# HLib-Comm-RS485.net
KiCad netlist of a schematic drawn in Altium Designer
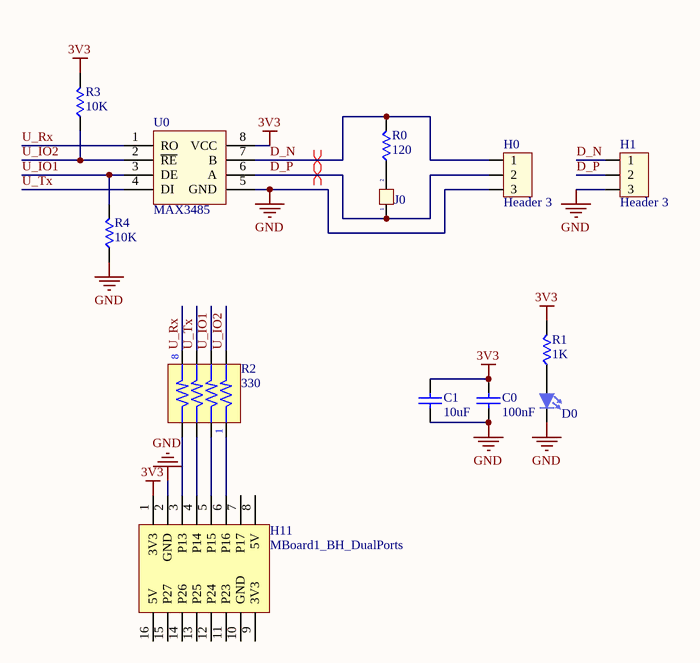
[diagram p0: HLib-Comm-RS485.SchDoc]

(export (version "E")
  (design (tool "Eeschema 10.0.6"))
  (components
    (comp (ref "C0")
      (value "100nF")
      (footprint "SM_0805_C_CERAMIC")
      (description "Non-polarity ceramic capacitor")
      (fields (field (name "Comment") "C_Ceramic") (field (name "PUBLISHER") "Altium Limited"))
      (libsource (lib "HLib_discrete_sch") (part "C_Ceramic"))
    )
    (comp (ref "C1")
      (value "10uF")
      (footprint "SM_0805_C_CERAMIC")
      (description "Non-polarity ceramic capacitor")
      (fields (field (name "Comment") "C_Ceramic") (field (name "PUBLISHER") "Altium Limited"))
      (libsource (lib "HLib_discrete_sch") (part "C_Ceramic"))
    )
    (comp (ref "D0")
      (value "LED")
      (footprint "SM_0805_LED")
      (fields (field (name "PUBLISHER") "Altium Limited"))
      (libsource (lib "HLib_discrete_sch") (part "LED"))
    )
    (comp (ref "H0")
      (value "Header 3")
      (footprint "TerminalBlock_3_5mm")
      (description "Header 3 (Green)")
      (libsource (lib "VioletofSun") (part "Hed3"))
    )
    (comp (ref "H1")
      (value "Header 3")
      (footprint "Hed3")
      (description "Header 3 (Green)")
      (libsource (lib "VioletofSun") (part "Hed3"))
    )
    (comp (ref "H11")
      (value "MBoard1_BH_DualPorts")
      (footprint "MBoard1_BH_DualPorts")
      (libsource (lib "Nhat_Lib") (part "MBoard1_BH_DualPorts"))
    )
    (comp (ref "J0") (value "Jumper 2") (footprint "J2") (libsource (lib "VioletofSun") (part "JP 2")))
    (comp (ref "R0")
      (value "120")
      (footprint "SM_0805_R")
      (description "Resistor")
      (fields (field (name "Comment") "R") (field (name "PUBLISHER") "Altium Limited"))
      (libsource (lib "HLib_discrete_sch") (part "R"))
    )
    (comp (ref "R1")
      (value "1K")
      (footprint "SM_0805_R")
      (description "Resistor")
      (fields (field (name "Comment") "R") (field (name "PUBLISHER") "Altium Limited"))
      (libsource (lib "HLib_discrete_sch") (part "R"))
    )
    (comp (ref "R2") (value "330") (footprint "RA4") (libsource (lib "Nhat_Lib") (part "RA4")))
    (comp (ref "R3")
      (value "10K")
      (footprint "SM_0805_R")
      (description "Resistor")
      (fields (field (name "Comment") "R") (field (name "PUBLISHER") "Altium Limited"))
      (libsource (lib "HLib_discrete_sch") (part "R"))
    )
    (comp (ref "R4")
      (value "10K")
      (footprint "SM_0805_R")
      (description "Resistor")
      (fields (field (name "Comment") "R") (field (name "PUBLISHER") "Altium Limited"))
      (libsource (lib "HLib_discrete_sch") (part "R"))
    )
    (comp (ref "U0")
      (value "MAX3485")
      (footprint "SO-8")
      (description "RS232 - RS485 (Same sn75176)")
      (libsource (lib "VioletofSun") (part "MAX485"))
    )
  )
  (nets
    (net (code "1") (name "/D_N") (class "Default")
      (node (ref "H0") (pin "1") (pinfunction "1_1") (pintype "passive"))
      (node (ref "H1") (pin "1") (pinfunction "1_1") (pintype "passive"))
      (node (ref "R0") (pin "2") (pinfunction "2_2") (pintype "passive"))
      (node (ref "U0") (pin "7") (pinfunction "B_7") (pintype "passive"))
    )
    (net (code "2") (name "/D_P") (class "Default")
      (node (ref "H0") (pin "2") (pinfunction "2_2") (pintype "passive"))
      (node (ref "H1") (pin "2") (pinfunction "2_2") (pintype "passive"))
      (node (ref "J0") (pin "1") (pinfunction "1_1") (pintype "passive"))
      (node (ref "U0") (pin "6") (pinfunction "A_6") (pintype "passive"))
    )
    (net (code "3") (name "/U_IO1") (class "Default")
      (node (ref "R2") (pin "4") (pinfunction "4_4") (pintype "passive"))
      (node (ref "R4") (pin "2") (pinfunction "2_2") (pintype "passive"))
      (node (ref "U0") (pin "3") (pinfunction "DE_3") (pintype "passive"))
    )
    (net (code "4") (name "/U_IO2") (class "Default")
      (node (ref "R2") (pin "2") (pinfunction "2_2") (pintype "passive"))
      (node (ref "R3") (pin "1") (pinfunction "1_1") (pintype "passive"))
      (node (ref "U0") (pin "2") (pinfunction "~{RE}_2") (pintype "passive"))
    )
    (net (code "5") (name "/U_Rx") (class "Default")
      (node (ref "R2") (pin "8") (pinfunction "8_8") (pintype "passive"))
      (node (ref "U0") (pin "1") (pinfunction "RO_1") (pintype "passive"))
    )
    (net (code "6") (name "/U_Tx") (class "Default")
      (node (ref "R2") (pin "6") (pinfunction "6_6") (pintype "passive"))
      (node (ref "U0") (pin "4") (pinfunction "DI_4") (pintype "passive"))
    )
    (net (code "7") (name "3V3") (class "Default")
      (node (ref "C0") (pin "2") (pinfunction "2_2") (pintype "passive"))
      (node (ref "C1") (pin "2") (pinfunction "2_2") (pintype "passive"))
      (node (ref "H11") (pin "1") (pinfunction "3V3_1") (pintype "passive"))
      (node (ref "R1") (pin "2") (pinfunction "2_2") (pintype "passive"))
      (node (ref "R3") (pin "2") (pinfunction "2_2") (pintype "passive"))
      (node (ref "U0") (pin "8") (pinfunction "VCC_8") (pintype "passive"))
    )
    (net (code "8") (name "GND") (class "Default")
      (node (ref "C0") (pin "1") (pinfunction "1_1") (pintype "passive"))
      (node (ref "C1") (pin "1") (pinfunction "1_1") (pintype "passive"))
      (node (ref "D0") (pin "2") (pinfunction "K_2") (pintype "passive"))
      (node (ref "H0") (pin "3") (pinfunction "3_3") (pintype "passive"))
      (node (ref "H1") (pin "3") (pinfunction "3_3") (pintype "passive"))
      (node (ref "H11") (pin "2") (pinfunction "GND_2") (pintype "passive"))
      (node (ref "R4") (pin "1") (pinfunction "1_1") (pintype "passive"))
      (node (ref "U0") (pin "5") (pinfunction "GND_5") (pintype "passive"))
    )
    (net (code "9") (name "Net-(D0-A)") (class "Default")
      (node (ref "D0") (pin "1") (pinfunction "A_1") (pintype "passive"))
      (node (ref "R1") (pin "1") (pinfunction "1_1") (pintype "passive"))
    )
    (net (code "10") (name "Net-(H11-P13)") (class "Default")
      (node (ref "H11") (pin "3") (pinfunction "P13_3") (pintype "passive"))
      (node (ref "R2") (pin "7") (pinfunction "7_7") (pintype "passive"))
    )
    (net (code "11") (name "Net-(H11-P14)") (class "Default")
      (node (ref "H11") (pin "4") (pinfunction "P14_4") (pintype "passive"))
      (node (ref "R2") (pin "5") (pinfunction "5_5") (pintype "passive"))
    )
    (net (code "12") (name "Net-(H11-P15)") (class "Default")
      (node (ref "H11") (pin "5") (pinfunction "P15_5") (pintype "passive"))
      (node (ref "R2") (pin "3") (pinfunction "3_3") (pintype "passive"))
    )
    (net (code "13") (name "Net-(H11-P16)") (class "Default")
      (node (ref "H11") (pin "6") (pinfunction "P16_6") (pintype "passive"))
      (node (ref "R2") (pin "1") (pinfunction "1_1") (pintype "passive"))
    )
    (net (code "14") (name "Net-(J0-Pad2)") (class "Default")
      (node (ref "J0") (pin "2") (pinfunction "2_2") (pintype "passive"))
      (node (ref "R0") (pin "1") (pinfunction "1_1") (pintype "passive"))
    )
    (net (code "15") (name "unconnected-(H11-3V3-Pad9)") (class "Default")
      (node (ref "H11") (pin "9") (pinfunction "3V3_9") (pintype "passive"))
    )
    (net (code "16") (name "unconnected-(H11-5V-Pad8)") (class "Default")
      (node (ref "H11") (pin "8") (pinfunction "5V_8") (pintype "passive"))
    )
    (net (code "17") (name "unconnected-(H11-5V-Pad16)") (class "Default")
      (node (ref "H11") (pin "16") (pinfunction "5V_16") (pintype "passive"))
    )
    (net (code "18") (name "unconnected-(H11-GND-Pad10)") (class "Default")
      (node (ref "H11") (pin "10") (pinfunction "GND_10") (pintype "passive"))
    )
    (net (code "19") (name "unconnected-(H11-P17-Pad7)") (class "Default")
      (node (ref "H11") (pin "7") (pinfunction "P17_7") (pintype "passive"))
    )
    (net (code "20") (name "unconnected-(H11-P23-Pad11)") (class "Default")
      (node (ref "H11") (pin "11") (pinfunction "P23_11") (pintype "passive"))
    )
    (net (code "21") (name "unconnected-(H11-P24-Pad12)") (class "Default")
      (node (ref "H11") (pin "12") (pinfunction "P24_12") (pintype "passive"))
    )
    (net (code "22") (name "unconnected-(H11-P25-Pad13)") (class "Default")
      (node (ref "H11") (pin "13") (pinfunction "P25_13") (pintype "passive"))
    )
    (net (code "23") (name "unconnected-(H11-P26-Pad14)") (class "Default")
      (node (ref "H11") (pin "14") (pinfunction "P26_14") (pintype "passive"))
    )
    (net (code "24") (name "unconnected-(H11-P27-Pad15)") (class "Default")
      (node (ref "H11") (pin "15") (pinfunction "P27_15") (pintype "passive"))
    )
  )
)
